# LampLed_-_Rev_A1.net
KiCad netlist of a schematic drawn in EAGLE
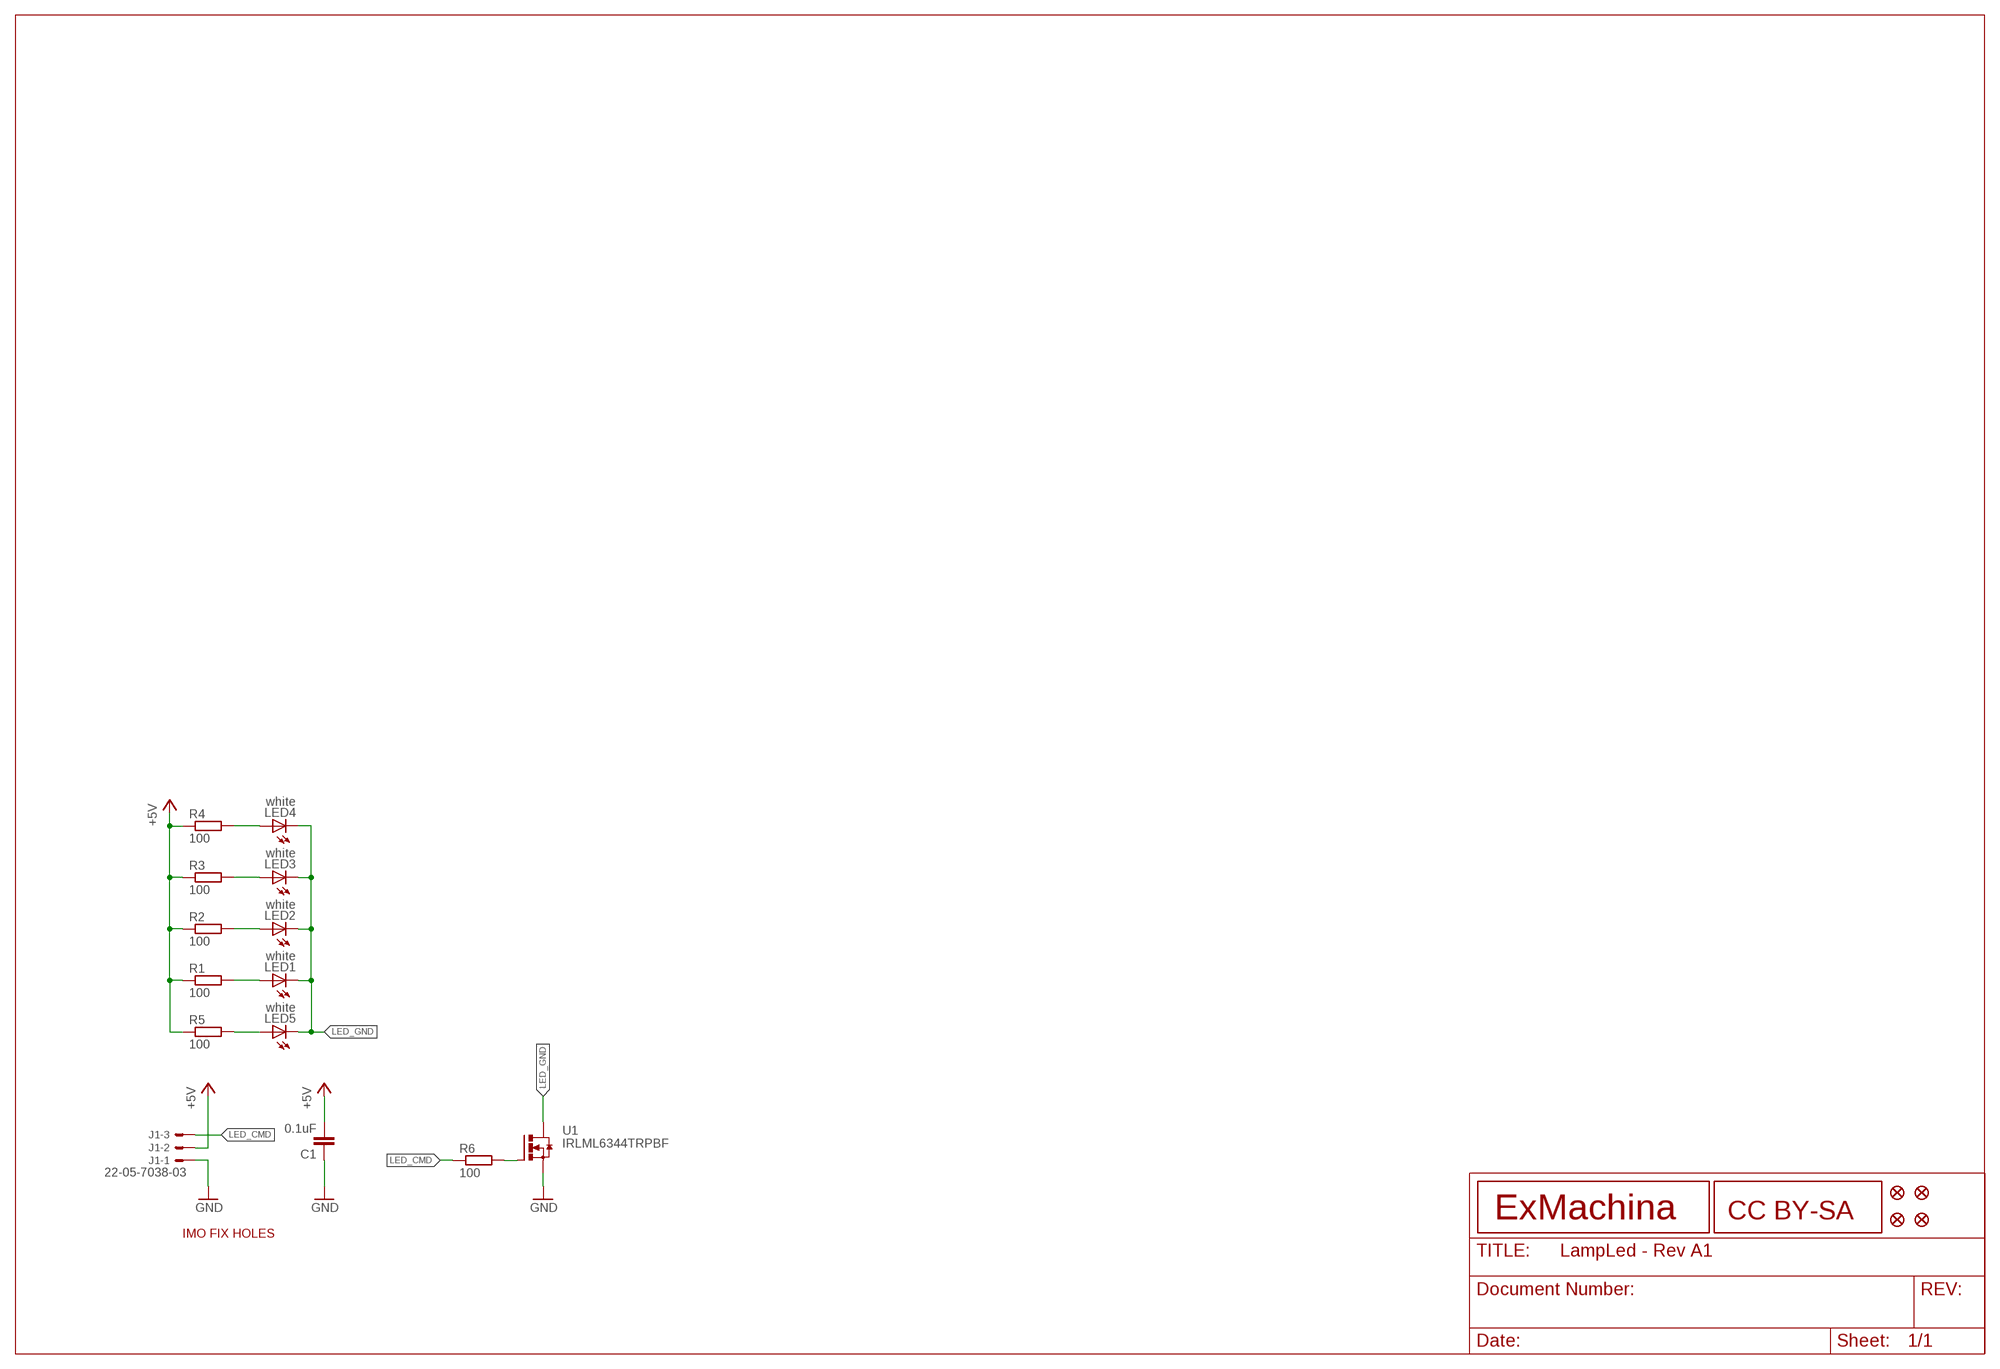
[diagram p0: schematic, sheet 1]

(export (version "E")
  (design (tool "Eeschema 10.0.6"))
  (components
    (comp (ref "C1")
      (value "0.1uF")
      (footprint "eagle-import:C0603")
      (libsource (lib "eagle-import") (part "C-EUC0603"))
    )
    (comp (ref "J1")
      (value "22-05-7038-03")
      (footprint "eagle-import:7395-03")
      (libsource (lib "eagle-import") (part "22-?-0305-7038"))
    )
    (comp (ref "JP1")
      (value "FIDUCIAL1X2")
      (footprint "eagle-import:FIDUCIAL-1X2")
      (libsource (lib "eagle-import") (part "FIDUCIAL1X2"))
    )
    (comp (ref "JP2")
      (value "FIDUCIAL1X2")
      (footprint "eagle-import:FIDUCIAL-1X2")
      (libsource (lib "eagle-import") (part "FIDUCIAL1X2"))
    )
    (comp (ref "JP3")
      (value "FIDUCIAL1X2")
      (footprint "eagle-import:FIDUCIAL-1X2")
      (libsource (lib "eagle-import") (part "FIDUCIAL1X2"))
    )
    (comp (ref "JP4")
      (value "FIDUCIAL1X2")
      (footprint "eagle-import:FIDUCIAL-1X2")
      (libsource (lib "eagle-import") (part "FIDUCIAL1X2"))
    )
    (comp (ref "LED1")
      (value "white")
      (footprint "eagle-import:CHIP-LED0603")
      (libsource (lib "eagle-import") (part "LEDCHIP-LED0603"))
    )
    (comp (ref "LED2")
      (value "white")
      (footprint "eagle-import:CHIP-LED0603")
      (libsource (lib "eagle-import") (part "LEDCHIP-LED0603"))
    )
    (comp (ref "LED3")
      (value "white")
      (footprint "eagle-import:CHIP-LED0603")
      (libsource (lib "eagle-import") (part "LEDCHIP-LED0603"))
    )
    (comp (ref "LED4")
      (value "white")
      (footprint "eagle-import:CHIP-LED0603")
      (libsource (lib "eagle-import") (part "LEDCHIP-LED0603"))
    )
    (comp (ref "LED5")
      (value "white")
      (footprint "eagle-import:CHIP-LED0603")
      (libsource (lib "eagle-import") (part "LEDCHIP-LED0603"))
    )
    (comp (ref "R1")
      (value "100")
      (footprint "eagle-import:R0603")
      (libsource (lib "eagle-import") (part "R-EU_R0603"))
    )
    (comp (ref "R2")
      (value "100")
      (footprint "eagle-import:R0603")
      (libsource (lib "eagle-import") (part "R-EU_R0603"))
    )
    (comp (ref "R3")
      (value "100")
      (footprint "eagle-import:R0603")
      (libsource (lib "eagle-import") (part "R-EU_R0603"))
    )
    (comp (ref "R4")
      (value "100")
      (footprint "eagle-import:R0603")
      (libsource (lib "eagle-import") (part "R-EU_R0603"))
    )
    (comp (ref "R5")
      (value "100")
      (footprint "eagle-import:R0603")
      (libsource (lib "eagle-import") (part "R-EU_R0603"))
    )
    (comp (ref "R6")
      (value "100")
      (footprint "eagle-import:R0603")
      (libsource (lib "eagle-import") (part "R-EU_R0603"))
    )
    (comp (ref "U$1")
      (value "IMO-FIXHOLES")
      (footprint "eagle-import:IMO-FIXHOLES")
      (libsource (lib "eagle-import") (part "IMO-FIXHOLES"))
    )
    (comp (ref "U$2")
      (value "EXMACHINA-LOGO-NAME")
      (footprint "eagle-import:EXM-LOGO-BASELINE")
      (libsource (lib "eagle-import") (part "EXMACHINA-LOGO-NAME"))
    )
    (comp (ref "U$3")
      (value "CC-BY-SA")
      (footprint "eagle-import:CC-BY-SA")
      (libsource (lib "eagle-import") (part "CC-BY-SA"))
    )
    (comp (ref "U1")
      (value "IRLML6344TRPBF")
      (footprint "eagle-import:SOT95P240X112-3N")
      (libsource (lib "eagle-import") (part "IRLML6344TRPBF"))
    )
  )
  (nets
    (net (code "1") (name "+5V") (class "Default")
      (node (ref "C1") (pin "2") (pinfunction "2_2") (pintype "passive"))
      (node (ref "J1") (pin "2") (pinfunction "S_2") (pintype "passive"))
      (node (ref "R1") (pin "1") (pinfunction "1_1") (pintype "passive"))
      (node (ref "R2") (pin "1") (pinfunction "1_1") (pintype "passive"))
      (node (ref "R3") (pin "1") (pinfunction "1_1") (pintype "passive"))
      (node (ref "R4") (pin "1") (pinfunction "1_1") (pintype "passive"))
      (node (ref "R5") (pin "1") (pinfunction "1_1") (pintype "passive"))
    )
    (net (code "2") (name "GND") (class "Default")
      (node (ref "C1") (pin "1") (pinfunction "1_1") (pintype "passive"))
      (node (ref "J1") (pin "1") (pinfunction "S_1") (pintype "passive"))
      (node (ref "U1") (pin "2") (pinfunction "S_2") (pintype "passive"))
    )
    (net (code "3") (name "LED_CMD") (class "Default")
      (node (ref "J1") (pin "3") (pinfunction "S_3") (pintype "passive"))
      (node (ref "R6") (pin "1") (pinfunction "1_1") (pintype "passive"))
    )
    (net (code "4") (name "LED_GND") (class "Default")
      (node (ref "LED1") (pin "C") (pinfunction "C_C") (pintype "passive"))
      (node (ref "LED2") (pin "C") (pinfunction "C_C") (pintype "passive"))
      (node (ref "LED3") (pin "C") (pinfunction "C_C") (pintype "passive"))
      (node (ref "LED4") (pin "C") (pinfunction "C_C") (pintype "passive"))
      (node (ref "LED5") (pin "C") (pinfunction "C_C") (pintype "passive"))
      (node (ref "U1") (pin "3") (pinfunction "D_3") (pintype "output"))
    )
    (net (code "5") (name "Net-(LED1-PadA)") (class "Default")
      (node (ref "LED1") (pin "A") (pinfunction "A_A") (pintype "passive"))
      (node (ref "R1") (pin "2") (pinfunction "2_2") (pintype "passive"))
    )
    (net (code "6") (name "Net-(LED2-PadA)") (class "Default")
      (node (ref "LED2") (pin "A") (pinfunction "A_A") (pintype "passive"))
      (node (ref "R2") (pin "2") (pinfunction "2_2") (pintype "passive"))
    )
    (net (code "7") (name "Net-(LED3-PadA)") (class "Default")
      (node (ref "LED3") (pin "A") (pinfunction "A_A") (pintype "passive"))
      (node (ref "R3") (pin "2") (pinfunction "2_2") (pintype "passive"))
    )
    (net (code "8") (name "Net-(LED4-PadA)") (class "Default")
      (node (ref "LED4") (pin "A") (pinfunction "A_A") (pintype "passive"))
      (node (ref "R4") (pin "2") (pinfunction "2_2") (pintype "passive"))
    )
    (net (code "9") (name "Net-(LED5-PadA)") (class "Default")
      (node (ref "LED5") (pin "A") (pinfunction "A_A") (pintype "passive"))
      (node (ref "R5") (pin "2") (pinfunction "2_2") (pintype "passive"))
    )
    (net (code "10") (name "Net-(U1-G)") (class "Default")
      (node (ref "R6") (pin "2") (pinfunction "2_2") (pintype "passive"))
      (node (ref "U1") (pin "1") (pinfunction "G_1") (pintype "input"))
    )
  )
)
